# SMPS_5V_A.net
KiCad netlist of a schematic drawn in Altium Designer
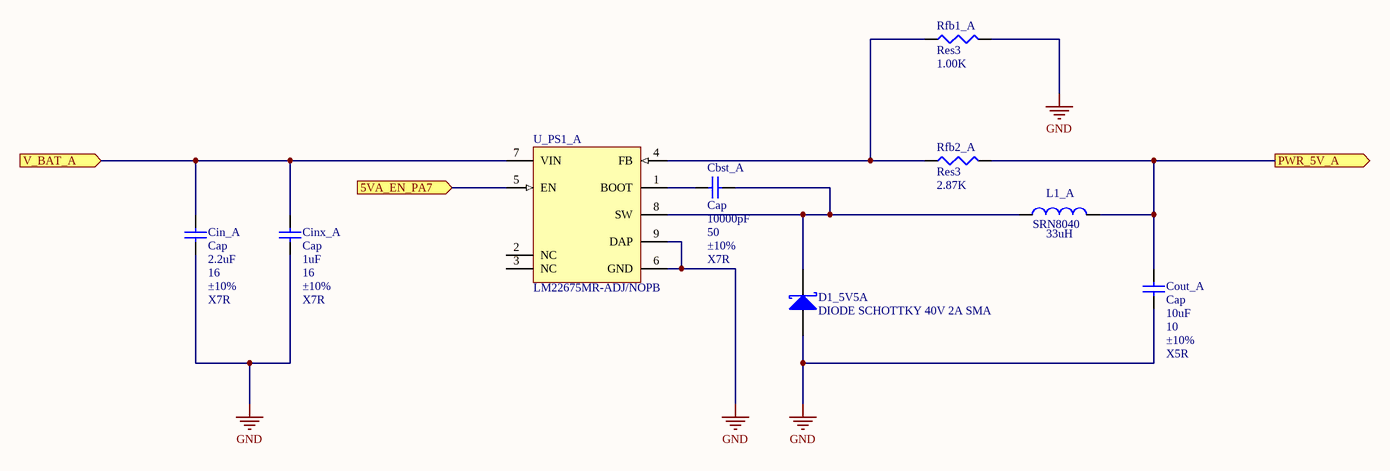
[diagram p0: SMPS_5V_A.SchDoc]

(export (version "E")
  (design (tool "Eeschema 10.0.6"))
  (components
    (comp (ref "Cbst_A")
      (value "Cap")
      (footprint "CAPC2012X09M")
      (description "CAP CER 10000pF 50v X7R 0805")
      (fields
        (field (name "ALTIUM_VALUE") "10000pF")
        (field (name "WV") "50")
        (field (name "TOLERANCE") "±10%")
        (field (name "TYPE") "X7R")
        (field (name "MPN") "C0805C103K5RACTU")
      )
      (libsource (lib "esd_library") (part "CAP-X7R-10000pF-50V-±10%"))
    )
    (comp (ref "Cinx_A")
      (value "Cap")
      (footprint "CAPC2012X09M")
      (description "CAP CER 1uF 16v X7R 0805")
      (fields
        (field (name "ALTIUM_VALUE") "1uF")
        (field (name "WV") "16")
        (field (name "TOLERANCE") "±10%")
        (field (name "TYPE") "X7R")
        (field (name "MPN") "C0805C105K4RACTU")
      )
      (libsource (lib "esd_library") (part "CAP-X7R-1uF-16V-±10%"))
    )
    (comp (ref "Cin_A")
      (value "Cap")
      (footprint "CAPC2012X09M")
      (description "CAP CER 2.2uF 16v X7R 0805")
      (fields
        (field (name "ALTIUM_VALUE") "2.2uF")
        (field (name "WV") "16")
        (field (name "TOLERANCE") "±10%")
        (field (name "TYPE") "X7R")
        (field (name "MPN") "C0805C225K4RACTU")
      )
      (libsource (lib "esd_library") (part "CAP-X7R-2.2uF-16V-±10%"))
    )
    (comp (ref "Cout_A")
      (value "Cap")
      (footprint "CAPC2012X09M")
      (description "CAP CER 10uF 10v X5R 0805")
      (fields
        (field (name "ALTIUM_VALUE") "10uF")
        (field (name "WV") "10")
        (field (name "TOLERANCE") "±10%")
        (field (name "TYPE") "X5R")
        (field (name "MPN") "C0805C106K8PACTU")
      )
      (libsource (lib "esd_library") (part "CAP-X5R-10uF-10V-±10%"))
    )
    (comp (ref "D1_5V5A")
      (value "DIODE SCHOTTKY 40V 2A SMA")
      (footprint "DIOM4326X23M")
      (description "Schottky Rectifier")
      (fields (field (name "MPN") "B240A-13-F"))
      (libsource (lib "esd_library") (part "DIODE SCHOTTKY 40V 2A SMA"))
    )
    (comp (ref "L1_A")
      (value "SRN8040")
      (footprint "INDP8080X40M")
      (description "FIXED IND 33UH 1.7A 145 MOHM SMD")
      (fields (field (name "MPN") "SRN8040-220M") (field (name "VAL") "33uH"))
      (libsource (lib "esd_library") (part "SRN8040"))
    )
    (comp (ref "Rfb1_A")
      (value "Res3")
      (footprint "RESC2112X05M")
      (description "RES SMD 1.00K OHM 1% 1/8W 0805")
      (fields (field (name "MPN") "CRCW08051K00FKEA") (field (name "ALTIUM_VALUE") "1.00K"))
      (libsource (lib "esd_library") (part "Resistor_1.00K"))
    )
    (comp (ref "Rfb2_A")
      (value "Res3")
      (footprint "RESC2112X05M")
      (description "RES SMD 2.87K OHM 1% 1/8W 0805")
      (fields (field (name "ALTIUM_VALUE") "2.87K") (field (name "MPN") "CRCW08052K87FKEA"))
      (libsource (lib "esd_library") (part "Resistor_2.87K"))
    )
    (comp (ref "U_PS1_A")
      (value "LM22675MR-ADJ/NOPB")
      (footprint "MRA08B_L")
      (description "1A SIMPLE SWITCHER®, Step-Down Voltage Regulator with Precision Enable, 8-pin PSOP, Pb-Free")
      (fields
        (field (name "MANUFACTURER") "National Semiconductor")
        (field (name "MPN") "LM22675MRE-ADJ/NOPB")
      )
      (libsource (lib "esd_library") (part "LM22675MR-ADJ/NOPB"))
    )
  )
  (nets
    (net (code "1") (name "/5VA_EN_PA7") (class "Default")
      (node (ref "U_PS1_A") (pin "5") (pinfunction "EN_5") (pintype "input"))
    )
    (net (code "2") (name "/PWR_5V_A") (class "Default")
      (node (ref "Cout_A") (pin "2") (pinfunction "2_2") (pintype "passive"))
      (node (ref "L1_A") (pin "2") (pinfunction "2_2") (pintype "passive"))
      (node (ref "Rfb2_A") (pin "2") (pinfunction "2_2") (pintype "passive"))
    )
    (net (code "3") (name "/V_BAT_A") (class "Default")
      (node (ref "Cin_A") (pin "2") (pinfunction "2_2") (pintype "passive"))
      (node (ref "Cinx_A") (pin "2") (pinfunction "2_2") (pintype "passive"))
      (node (ref "U_PS1_A") (pin "7") (pinfunction "VIN_7") (pintype "power_in"))
    )
    (net (code "4") (name "GND") (class "Default")
      (node (ref "Cin_A") (pin "1") (pinfunction "1_1") (pintype "passive"))
      (node (ref "Cinx_A") (pin "1") (pinfunction "1_1") (pintype "passive"))
      (node (ref "Cout_A") (pin "1") (pinfunction "1_1") (pintype "passive"))
      (node (ref "D1_5V5A") (pin "2") (pinfunction "A_2") (pintype "passive"))
      (node (ref "Rfb1_A") (pin "2") (pinfunction "2_2") (pintype "passive"))
      (node (ref "U_PS1_A") (pin "6") (pinfunction "GND_6") (pintype "power_in"))
      (node (ref "U_PS1_A") (pin "9") (pinfunction "DAP_9") (pintype "power_in"))
    )
    (net (code "5") (name "Net-(D1_5V5A-K)") (class "Default")
      (node (ref "Cbst_A") (pin "2") (pinfunction "2_2") (pintype "passive"))
      (node (ref "D1_5V5A") (pin "1") (pinfunction "K_1") (pintype "passive"))
      (node (ref "L1_A") (pin "1") (pinfunction "1_1") (pintype "passive"))
      (node (ref "U_PS1_A") (pin "8") (pinfunction "SW_8") (pintype "power_in"))
    )
    (net (code "6") (name "Net-(U_PS1_A-BOOT)") (class "Default")
      (node (ref "Cbst_A") (pin "1") (pinfunction "1_1") (pintype "passive"))
      (node (ref "U_PS1_A") (pin "1") (pinfunction "BOOT_1") (pintype "passive"))
    )
    (net (code "7") (name "Net-(U_PS1_A-FB)") (class "Default")
      (node (ref "Rfb1_A") (pin "1") (pinfunction "1_1") (pintype "passive"))
      (node (ref "Rfb2_A") (pin "1") (pinfunction "1_1") (pintype "passive"))
      (node (ref "U_PS1_A") (pin "4") (pinfunction "FB_4") (pintype "input"))
    )
    (net (code "8") (name "unconnected-(U_PS1_A-NC-Pad2)") (class "Default")
      (node (ref "U_PS1_A") (pin "2") (pinfunction "NC_2") (pintype "passive"))
    )
    (net (code "9") (name "unconnected-(U_PS1_A-NC-Pad3)") (class "Default")
      (node (ref "U_PS1_A") (pin "3") (pinfunction "NC_3") (pintype "passive"))
    )
  )
)
